# PSocC_Motor_Driver_Design_2.net
KiCad netlist of a schematic drawn in EAGLE
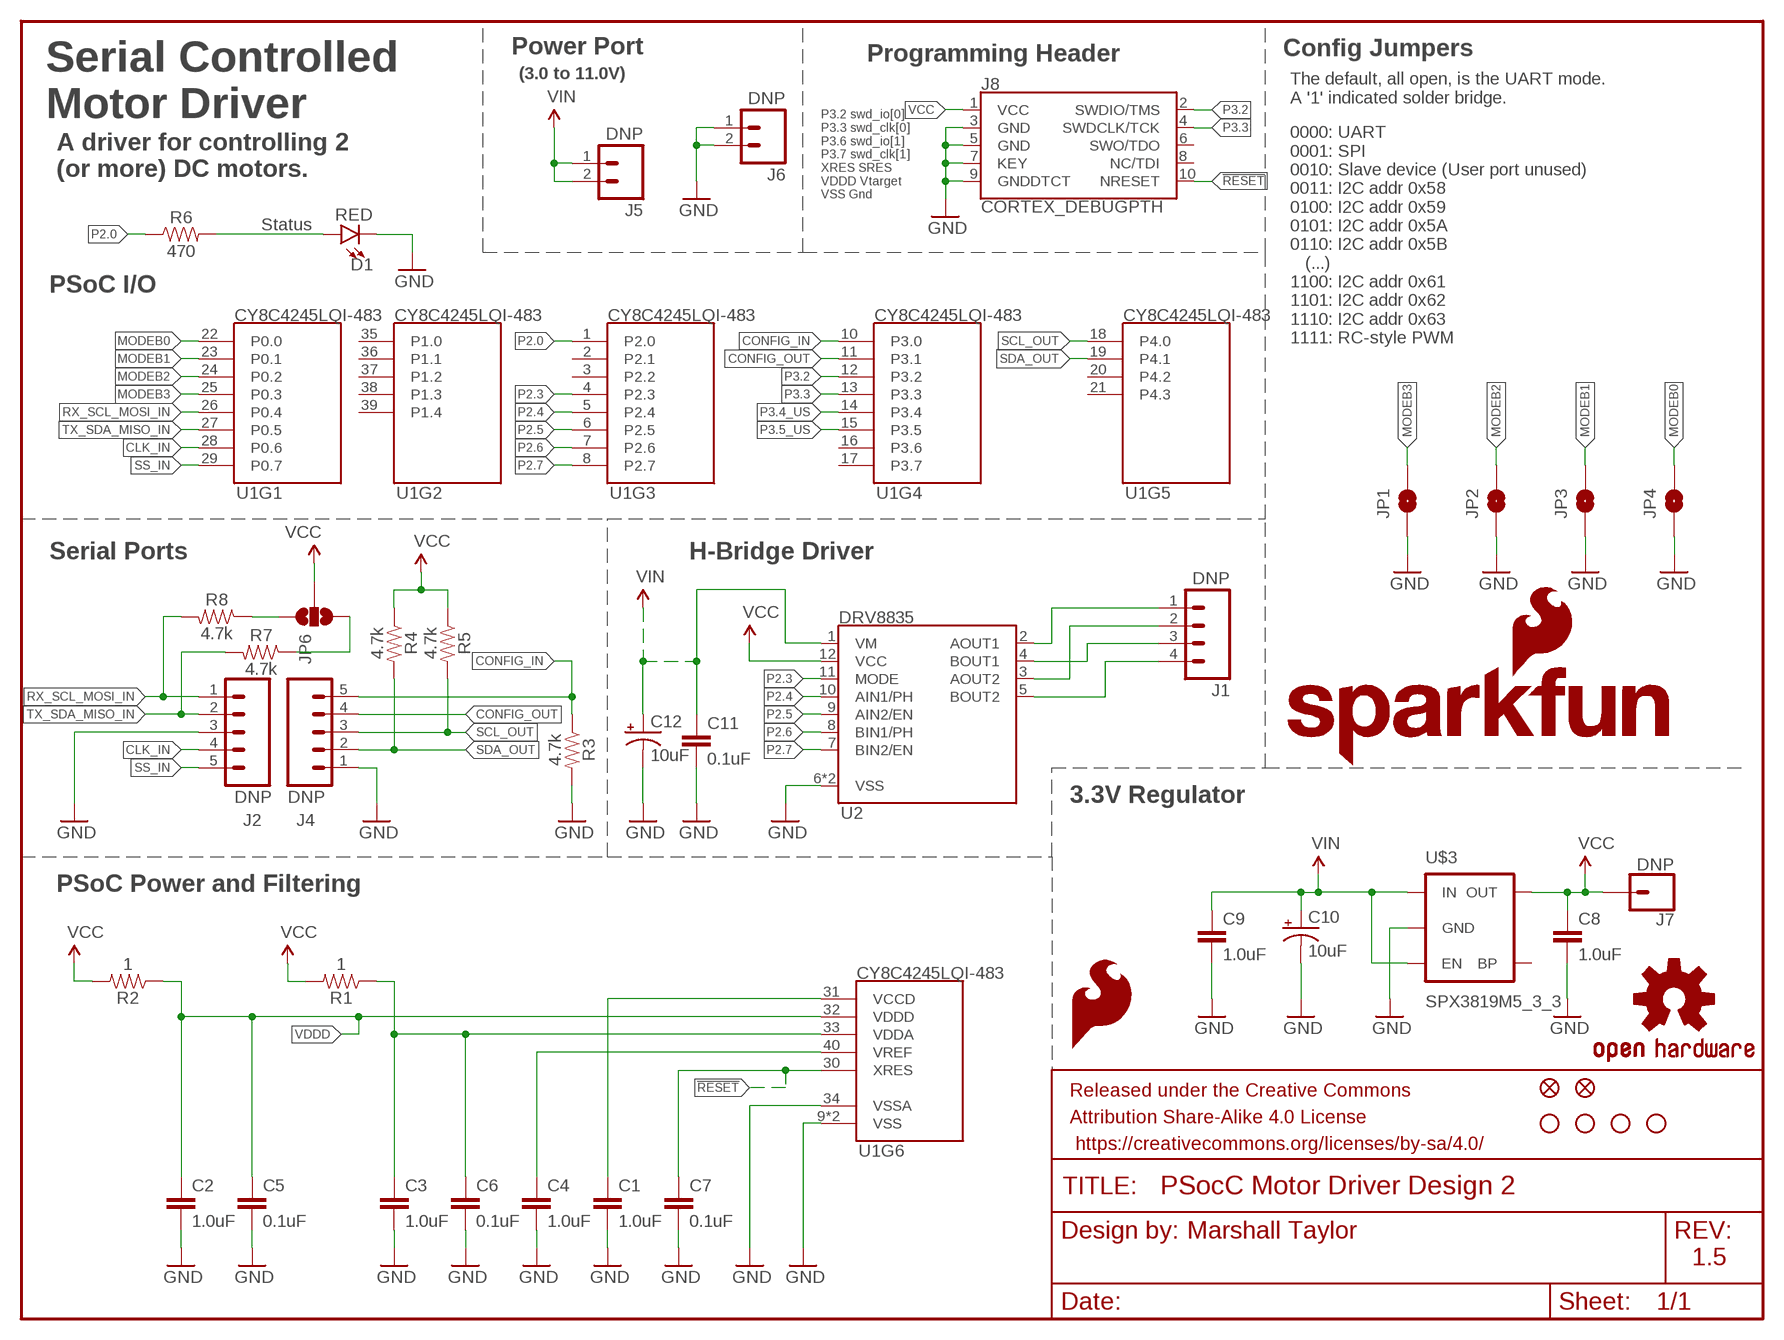
[diagram p0: schematic, sheet 1]

(export (version "E")
  (design (tool "Eeschema 10.0.6"))
  (components
    (comp (ref "C1")
      (value "1.0uF")
      (footprint "eagle-import:0402")
      (libsource (lib "eagle-import") (part "1.0UF-0402-16V-10%"))
    )
    (comp (ref "C2")
      (value "1.0uF")
      (footprint "eagle-import:0402")
      (libsource (lib "eagle-import") (part "1.0UF-0402-16V-10%"))
    )
    (comp (ref "C3")
      (value "1.0uF")
      (footprint "eagle-import:0402")
      (libsource (lib "eagle-import") (part "1.0UF-0402-16V-10%"))
    )
    (comp (ref "C4")
      (value "1.0uF")
      (footprint "eagle-import:0402")
      (libsource (lib "eagle-import") (part "1.0UF-0402-16V-10%"))
    )
    (comp (ref "C5")
      (value "0.1uF")
      (footprint "eagle-import:0402")
      (libsource (lib "eagle-import") (part "0.1UF-0402-16V-10%"))
    )
    (comp (ref "C6")
      (value "0.1uF")
      (footprint "eagle-import:0402")
      (libsource (lib "eagle-import") (part "0.1UF-0402-16V-10%"))
    )
    (comp (ref "C7")
      (value "0.1uF")
      (footprint "eagle-import:0402")
      (libsource (lib "eagle-import") (part "0.1UF-0402-16V-10%"))
    )
    (comp (ref "C8")
      (value "1.0uF")
      (footprint "eagle-import:0402")
      (libsource (lib "eagle-import") (part "1.0UF-0402-16V-10%"))
    )
    (comp (ref "C9")
      (value "1.0uF")
      (footprint "eagle-import:0402")
      (libsource (lib "eagle-import") (part "1.0UF-0402-16V-10%"))
    )
    (comp (ref "C10")
      (value "10uF")
      (footprint "eagle-import:EIA3216")
      (libsource (lib "eagle-import") (part "10UF-POLAR-EIA3216-16V-10%(TANT)"))
    )
    (comp (ref "C11")
      (value "0.1uF")
      (footprint "eagle-import:0402")
      (libsource (lib "eagle-import") (part "0.1UF-0402-16V-10%"))
    )
    (comp (ref "C12")
      (value "10uF")
      (footprint "eagle-import:EIA3216")
      (libsource (lib "eagle-import") (part "10UF-POLAR-EIA3216-16V-10%(TANT)"))
    )
    (comp (ref "D1")
      (value "RED")
      (footprint "eagle-import:LED-0603")
      (libsource (lib "eagle-import") (part "LED-RED0603"))
    )
    (comp (ref "FD1")
      (value "FIDUCIALUFIDUCIAL")
      (footprint "eagle-import:MICRO-FIDUCIAL")
      (libsource (lib "eagle-import") (part "FIDUCIALUFIDUCIAL"))
    )
    (comp (ref "FD2")
      (value "FIDUCIALUFIDUCIAL")
      (footprint "eagle-import:MICRO-FIDUCIAL")
      (libsource (lib "eagle-import") (part "FIDUCIALUFIDUCIAL"))
    )
    (comp (ref "FRAME1")
      (value "FRAME-LETTER")
      (footprint "eagle-import:CREATIVE_COMMONS")
      (libsource (lib "eagle-import") (part "FRAME-LETTER"))
    )
    (comp (ref "H1")
      (value "STAND-OFF")
      (footprint "eagle-import:STAND-OFF")
      (libsource (lib "eagle-import") (part "STAND-OFF"))
    )
    (comp (ref "H2")
      (value "STAND-OFF")
      (footprint "eagle-import:STAND-OFF")
      (libsource (lib "eagle-import") (part "STAND-OFF"))
    )
    (comp (ref "H3")
      (value "STAND-OFF")
      (footprint "eagle-import:STAND-OFF")
      (libsource (lib "eagle-import") (part "STAND-OFF"))
    )
    (comp (ref "H4")
      (value "STAND-OFF")
      (footprint "eagle-import:STAND-OFF")
      (libsource (lib "eagle-import") (part "STAND-OFF"))
    )
    (comp (ref "J1")
      (value "DNP")
      (footprint "eagle-import:1X04")
      (libsource (lib "eagle-import") (part "M04PTH"))
    )
    (comp (ref "J2")
      (value "DNP")
      (footprint "eagle-import:1X05")
      (libsource (lib "eagle-import") (part "M05PTH"))
    )
    (comp (ref "J4")
      (value "DNP")
      (footprint "eagle-import:1X05")
      (libsource (lib "eagle-import") (part "M05PTH"))
    )
    (comp (ref "J5")
      (value "DNP")
      (footprint "eagle-import:1X02")
      (libsource (lib "eagle-import") (part "M02PTH"))
    )
    (comp (ref "J6")
      (value "DNP")
      (footprint "eagle-import:1X02")
      (libsource (lib "eagle-import") (part "M02PTH"))
    )
    (comp (ref "J7")
      (value "DNP")
      (footprint "eagle-import:1X01")
      (libsource (lib "eagle-import") (part "CONN_01PTH"))
    )
    (comp (ref "J8")
      (value "CORTEX_DEBUGPTH")
      (footprint "eagle-import:2X5-PTH-1.27MM")
      (libsource (lib "eagle-import") (part "CORTEX_DEBUGPTH"))
    )
    (comp (ref "JP1")
      (value "JUMPER-PAD-2")
      (footprint "eagle-import:PAD-JUMPER-2-NO_YES_SILK")
      (libsource (lib "eagle-import") (part "JUMPER-PAD-2-NOYES_SILK"))
    )
    (comp (ref "JP2")
      (value "JUMPER-PAD-2")
      (footprint "eagle-import:PAD-JUMPER-2-NO_YES_SILK")
      (libsource (lib "eagle-import") (part "JUMPER-PAD-2-NOYES_SILK"))
    )
    (comp (ref "JP3")
      (value "JUMPER-PAD-2")
      (footprint "eagle-import:PAD-JUMPER-2-NO_YES_SILK")
      (libsource (lib "eagle-import") (part "JUMPER-PAD-2-NOYES_SILK"))
    )
    (comp (ref "JP4")
      (value "JUMPER-PAD-2")
      (footprint "eagle-import:PAD-JUMPER-2-NO_YES_SILK")
      (libsource (lib "eagle-import") (part "JUMPER-PAD-2-NOYES_SILK"))
    )
    (comp (ref "JP6")
      (value "JUMPER-PAD-3-NOYES_SILK")
      (footprint "eagle-import:PAD-JUMPER-3-NO_YES_SILK")
      (libsource (lib "eagle-import") (part "JUMPER-PAD-3-NOYES_SILK"))
    )
    (comp (ref "LOGO1")
      (value "SFE_LOGO_FLAME.1_INCH")
      (footprint "eagle-import:SFE_LOGO_FLAME_.1")
      (libsource (lib "eagle-import") (part "SFE_LOGO_FLAME.1_INCH"))
    )
    (comp (ref "LOGO2")
      (value "OSHW-LOGOMINI")
      (footprint "eagle-import:OSHW-LOGO-MINI")
      (libsource (lib "eagle-import") (part "OSHW-LOGOMINI"))
    )
    (comp (ref "LOGO3")
      (value "SFE_LOGO_NAME_FLAME.1_INCH")
      (footprint "eagle-import:SFE_LOGO_NAME_FLAME_.1")
      (libsource (lib "eagle-import") (part "SFE_LOGO_NAME_FLAME.1_INCH"))
    )
    (comp (ref "R1")
      (value "1")
      (footprint "eagle-import:0603")
      (libsource (lib "eagle-import") (part "1OHM-0603-1/10W-1%"))
    )
    (comp (ref "R2")
      (value "1")
      (footprint "eagle-import:0603")
      (libsource (lib "eagle-import") (part "1OHM-0603-1/10W-1%"))
    )
    (comp (ref "R3")
      (value "4.7k")
      (footprint "eagle-import:0603")
      (libsource (lib "eagle-import") (part "4.7KOHM-0603-1/10W-1%"))
    )
    (comp (ref "R4")
      (value "4.7k")
      (footprint "eagle-import:0603")
      (libsource (lib "eagle-import") (part "4.7KOHM-0603-1/10W-1%"))
    )
    (comp (ref "R5")
      (value "4.7k")
      (footprint "eagle-import:0603")
      (libsource (lib "eagle-import") (part "4.7KOHM-0603-1/10W-1%"))
    )
    (comp (ref "R6")
      (value "470")
      (footprint "eagle-import:0603")
      (libsource (lib "eagle-import") (part "470OHM-0603-1/10W-1%"))
    )
    (comp (ref "R7")
      (value "4.7k")
      (footprint "eagle-import:0603")
      (libsource (lib "eagle-import") (part "4.7KOHM-0603-1/10W-1%"))
    )
    (comp (ref "R8")
      (value "4.7k")
      (footprint "eagle-import:0603")
      (libsource (lib "eagle-import") (part "4.7KOHM-0603-1/10W-1%"))
    )
    (comp (ref "U$3")
      (value "SPX3819M5_3_3")
      (footprint "eagle-import:SOT-23-5-VREG")
      (libsource (lib "eagle-import") (part "SPX3819"))
    )
    (comp (ref "U1")
      (value "CY8C4245LQI-483")
      (footprint "eagle-import:QFN-40")
      (libsource (lib "eagle-import") (part "CY8C4245LQI"))
    )
    (comp (ref "U2")
      (value "DRV8835")
      (footprint "eagle-import:WSON-12")
      (fields (field (name "PROD_ID") "IC-13342"))
      (libsource (lib "eagle-import") (part "DRV883X"))
    )
  )
  (nets
    (net (code "1") (name "/~{RESET}") (class "Default")
      (node (ref "C7") (pin "1") (pinfunction "1_1") (pintype "passive"))
      (node (ref "J8") (pin "10") (pinfunction "NRESET_10") (pintype "bidirectional"))
      (node (ref "U1") (pin "30") (pinfunction "XRES_30") (pintype "bidirectional"))
    )
    (net (code "2") (name "CLK_IN") (class "Default")
      (node (ref "J2") (pin "4") (pinfunction "4_4") (pintype "passive"))
      (node (ref "U1") (pin "28") (pinfunction "P0.6_28") (pintype "bidirectional"))
    )
    (net (code "3") (name "CONFIG_IN") (class "Default")
      (node (ref "J4") (pin "5") (pinfunction "5_5") (pintype "passive"))
      (node (ref "R3") (pin "1") (pinfunction "1_1") (pintype "passive"))
      (node (ref "U1") (pin "10") (pinfunction "P3.0_10") (pintype "bidirectional"))
    )
    (net (code "4") (name "CONFIG_OUT") (class "Default")
      (node (ref "J4") (pin "4") (pinfunction "4_4") (pintype "passive"))
      (node (ref "U1") (pin "11") (pinfunction "P3.1_11") (pintype "bidirectional"))
    )
    (net (code "5") (name "GND") (class "Default")
      (node (ref "C1") (pin "2") (pinfunction "2_2") (pintype "passive"))
      (node (ref "C10") (pin "-") (pinfunction "-_-") (pintype "passive"))
      (node (ref "C11") (pin "2") (pinfunction "2_2") (pintype "passive"))
      (node (ref "C12") (pin "-") (pinfunction "-_-") (pintype "passive"))
      (node (ref "C2") (pin "2") (pinfunction "2_2") (pintype "passive"))
      (node (ref "C3") (pin "2") (pinfunction "2_2") (pintype "passive"))
      (node (ref "C4") (pin "2") (pinfunction "2_2") (pintype "passive"))
      (node (ref "C5") (pin "2") (pinfunction "2_2") (pintype "passive"))
      (node (ref "C6") (pin "2") (pinfunction "2_2") (pintype "passive"))
      (node (ref "C7") (pin "2") (pinfunction "2_2") (pintype "passive"))
      (node (ref "C8") (pin "2") (pinfunction "2_2") (pintype "passive"))
      (node (ref "C9") (pin "2") (pinfunction "2_2") (pintype "passive"))
      (node (ref "D1") (pin "C") (pinfunction "C_C") (pintype "passive"))
      (node (ref "J2") (pin "3") (pinfunction "3_3") (pintype "passive"))
      (node (ref "J4") (pin "1") (pinfunction "1_1") (pintype "passive"))
      (node (ref "J6") (pin "1") (pinfunction "1_1") (pintype "passive"))
      (node (ref "J6") (pin "2") (pinfunction "2_2") (pintype "passive"))
      (node (ref "J8") (pin "3") (pinfunction "GND_3") (pintype "bidirectional"))
      (node (ref "J8") (pin "5") (pinfunction "GND_5") (pintype "bidirectional"))
      (node (ref "J8") (pin "7") (pinfunction "KEY_7") (pintype "bidirectional"))
      (node (ref "J8") (pin "9") (pinfunction "GNDDTCT_9") (pintype "bidirectional"))
      (node (ref "JP1") (pin "1") (pinfunction "1_1") (pintype "passive"))
      (node (ref "JP2") (pin "1") (pinfunction "1_1") (pintype "passive"))
      (node (ref "JP3") (pin "1") (pinfunction "1_1") (pintype "passive"))
      (node (ref "JP4") (pin "1") (pinfunction "1_1") (pintype "passive"))
      (node (ref "R3") (pin "2") (pinfunction "2_2") (pintype "passive"))
      (node (ref "U$3") (pin "2") (pinfunction "GND_2") (pintype "input"))
      (node (ref "U1") (pin "34") (pinfunction "VSSA_34") (pintype "bidirectional"))
      (node (ref "U1") (pin "9") (pinfunction "VSS_9") (pintype "bidirectional"))
      (node (ref "U1") (pin "EP") (pinfunction "VSS_EP") (pintype "bidirectional"))
      (node (ref "U2") (pin "6") (pinfunction "VSS_6") (pintype "bidirectional"))
      (node (ref "U2") (pin "PAD") (pinfunction "VSS_PAD") (pintype "bidirectional"))
    )
    (net (code "6") (name "MODEB0") (class "Default")
      (node (ref "JP4") (pin "2") (pinfunction "2_2") (pintype "passive"))
      (node (ref "U1") (pin "22") (pinfunction "P0.0_22") (pintype "bidirectional"))
    )
    (net (code "7") (name "MODEB1") (class "Default")
      (node (ref "JP3") (pin "2") (pinfunction "2_2") (pintype "passive"))
      (node (ref "U1") (pin "23") (pinfunction "P0.1_23") (pintype "bidirectional"))
    )
    (net (code "8") (name "MODEB2") (class "Default")
      (node (ref "JP2") (pin "2") (pinfunction "2_2") (pintype "passive"))
      (node (ref "U1") (pin "24") (pinfunction "P0.2_24") (pintype "bidirectional"))
    )
    (net (code "9") (name "MODEB3") (class "Default")
      (node (ref "JP1") (pin "2") (pinfunction "2_2") (pintype "passive"))
      (node (ref "U1") (pin "25") (pinfunction "P0.3_25") (pintype "bidirectional"))
    )
    (net (code "10") (name "Net-(D1-PadA)") (class "Default")
      (node (ref "D1") (pin "A") (pinfunction "A_A") (pintype "passive"))
      (node (ref "R6") (pin "2") (pinfunction "2_2") (pintype "passive"))
    )
    (net (code "11") (name "Net-(JP6-Pad1)") (class "Default")
      (node (ref "JP6") (pin "1") (pinfunction "1_1") (pintype "passive"))
      (node (ref "R8") (pin "1") (pinfunction "1_1") (pintype "passive"))
    )
    (net (code "12") (name "Net-(JP6-Pad3)") (class "Default")
      (node (ref "JP6") (pin "3") (pinfunction "3_3") (pintype "passive"))
      (node (ref "R7") (pin "1") (pinfunction "1_1") (pintype "passive"))
    )
    (net (code "13") (name "Net-(U1F-VCCD)") (class "Default")
      (node (ref "C1") (pin "1") (pinfunction "1_1") (pintype "passive"))
      (node (ref "U1") (pin "31") (pinfunction "VCCD_31") (pintype "bidirectional"))
    )
    (net (code "14") (name "Net-(U1F-VDDA)") (class "Default")
      (node (ref "C3") (pin "1") (pinfunction "1_1") (pintype "passive"))
      (node (ref "C6") (pin "1") (pinfunction "1_1") (pintype "passive"))
      (node (ref "R1") (pin "1") (pinfunction "1_1") (pintype "passive"))
      (node (ref "U1") (pin "33") (pinfunction "VDDA_33") (pintype "bidirectional"))
    )
    (net (code "15") (name "Net-(U1F-VREF)") (class "Default")
      (node (ref "C4") (pin "1") (pinfunction "1_1") (pintype "passive"))
      (node (ref "U1") (pin "40") (pinfunction "VREF_40") (pintype "bidirectional"))
    )
    (net (code "16") (name "Net-(U2-AOUT1)") (class "Default")
      (node (ref "J1") (pin "1") (pinfunction "1_1") (pintype "passive"))
      (node (ref "U2") (pin "2") (pinfunction "AOUT1_2") (pintype "bidirectional"))
    )
    (net (code "17") (name "Net-(U2-AOUT2)") (class "Default")
      (node (ref "J1") (pin "2") (pinfunction "2_2") (pintype "passive"))
      (node (ref "U2") (pin "3") (pinfunction "AOUT2_3") (pintype "bidirectional"))
    )
    (net (code "18") (name "Net-(U2-BOUT1)") (class "Default")
      (node (ref "J1") (pin "3") (pinfunction "3_3") (pintype "passive"))
      (node (ref "U2") (pin "4") (pinfunction "BOUT1_4") (pintype "bidirectional"))
    )
    (net (code "19") (name "Net-(U2-BOUT2)") (class "Default")
      (node (ref "J1") (pin "4") (pinfunction "4_4") (pintype "passive"))
      (node (ref "U2") (pin "5") (pinfunction "BOUT2_5") (pintype "bidirectional"))
    )
    (net (code "20") (name "P2.0") (class "Default")
      (node (ref "R6") (pin "1") (pinfunction "1_1") (pintype "passive"))
      (node (ref "U1") (pin "1") (pinfunction "P2.0_1") (pintype "bidirectional"))
    )
    (net (code "21") (name "P2.3") (class "Default")
      (node (ref "U1") (pin "4") (pinfunction "P2.3_4") (pintype "bidirectional"))
      (node (ref "U2") (pin "11") (pinfunction "MODE_11") (pintype "bidirectional"))
    )
    (net (code "22") (name "P2.4") (class "Default")
      (node (ref "U1") (pin "5") (pinfunction "P2.4_5") (pintype "bidirectional"))
      (node (ref "U2") (pin "10") (pinfunction "AIN1/PH_10") (pintype "bidirectional"))
    )
    (net (code "23") (name "P2.5") (class "Default")
      (node (ref "U1") (pin "6") (pinfunction "P2.5_6") (pintype "bidirectional"))
      (node (ref "U2") (pin "9") (pinfunction "AIN2/EN_9") (pintype "bidirectional"))
    )
    (net (code "24") (name "P2.6") (class "Default")
      (node (ref "U1") (pin "7") (pinfunction "P2.6_7") (pintype "bidirectional"))
      (node (ref "U2") (pin "8") (pinfunction "BIN1/PH_8") (pintype "bidirectional"))
    )
    (net (code "25") (name "P2.7") (class "Default")
      (node (ref "U1") (pin "8") (pinfunction "P2.7_8") (pintype "bidirectional"))
      (node (ref "U2") (pin "7") (pinfunction "BIN2/EN_7") (pintype "bidirectional"))
    )
    (net (code "26") (name "P3.2") (class "Default")
      (node (ref "J8") (pin "2") (pinfunction "SWDIO/TMS_2") (pintype "bidirectional"))
      (node (ref "U1") (pin "12") (pinfunction "P3.2_12") (pintype "bidirectional"))
    )
    (net (code "27") (name "P3.3") (class "Default")
      (node (ref "J8") (pin "4") (pinfunction "SWDCLK/TCK_4") (pintype "bidirectional"))
      (node (ref "U1") (pin "13") (pinfunction "P3.3_13") (pintype "bidirectional"))
    )
    (net (code "28") (name "P3.4_US") (class "Default")
      (node (ref "U1") (pin "14") (pinfunction "P3.4_14") (pintype "bidirectional"))
    )
    (net (code "29") (name "P3.5_US") (class "Default")
      (node (ref "U1") (pin "15") (pinfunction "P3.5_15") (pintype "bidirectional"))
    )
    (net (code "30") (name "RX_SCL_MOSI_IN") (class "Default")
      (node (ref "J2") (pin "1") (pinfunction "1_1") (pintype "passive"))
      (node (ref "R8") (pin "2") (pinfunction "2_2") (pintype "passive"))
      (node (ref "U1") (pin "26") (pinfunction "P0.4_26") (pintype "bidirectional"))
    )
    (net (code "31") (name "SCL_OUT") (class "Default")
      (node (ref "J4") (pin "3") (pinfunction "3_3") (pintype "passive"))
      (node (ref "R5") (pin "2") (pinfunction "2_2") (pintype "passive"))
      (node (ref "U1") (pin "18") (pinfunction "P4.0_18") (pintype "bidirectional"))
    )
    (net (code "32") (name "SDA_OUT") (class "Default")
      (node (ref "J4") (pin "2") (pinfunction "2_2") (pintype "passive"))
      (node (ref "R4") (pin "2") (pinfunction "2_2") (pintype "passive"))
      (node (ref "U1") (pin "19") (pinfunction "P4.1_19") (pintype "bidirectional"))
    )
    (net (code "33") (name "SS_IN") (class "Default")
      (node (ref "J2") (pin "5") (pinfunction "5_5") (pintype "passive"))
      (node (ref "U1") (pin "29") (pinfunction "P0.7_29") (pintype "bidirectional"))
    )
    (net (code "34") (name "TX_SDA_MISO_IN") (class "Default")
      (node (ref "J2") (pin "2") (pinfunction "2_2") (pintype "passive"))
      (node (ref "R7") (pin "2") (pinfunction "2_2") (pintype "passive"))
      (node (ref "U1") (pin "27") (pinfunction "P0.5_27") (pintype "bidirectional"))
    )
    (net (code "35") (name "VCC") (class "Default")
      (node (ref "C8") (pin "1") (pinfunction "1_1") (pintype "passive"))
      (node (ref "J7") (pin "1") (pinfunction "1_1") (pintype "passive"))
      (node (ref "J8") (pin "1") (pinfunction "VCC_1") (pintype "bidirectional"))
      (node (ref "JP6") (pin "2") (pinfunction "2_2") (pintype "passive"))
      (node (ref "R1") (pin "2") (pinfunction "2_2") (pintype "passive"))
      (node (ref "R2") (pin "2") (pinfunction "2_2") (pintype "passive"))
      (node (ref "R4") (pin "1") (pinfunction "1_1") (pintype "passive"))
      (node (ref "R5") (pin "1") (pinfunction "1_1") (pintype "passive"))
      (node (ref "U$3") (pin "5") (pinfunction "OUT_5") (pintype "passive"))
      (node (ref "U2") (pin "12") (pinfunction "VCC_12") (pintype "bidirectional"))
    )
    (net (code "36") (name "VDDD") (class "Default")
      (node (ref "C2") (pin "1") (pinfunction "1_1") (pintype "passive"))
      (node (ref "C5") (pin "1") (pinfunction "1_1") (pintype "passive"))
      (node (ref "R2") (pin "1") (pinfunction "1_1") (pintype "passive"))
      (node (ref "U1") (pin "32") (pinfunction "VDDD_32") (pintype "bidirectional"))
    )
    (net (code "37") (name "VIN") (class "Default")
      (node (ref "C10") (pin "+") (pinfunction "+_+") (pintype "passive"))
      (node (ref "C11") (pin "1") (pinfunction "1_1") (pintype "passive"))
      (node (ref "C12") (pin "+") (pinfunction "+_+") (pintype "passive"))
      (node (ref "C9") (pin "1") (pinfunction "1_1") (pintype "passive"))
      (node (ref "J5") (pin "1") (pinfunction "1_1") (pintype "passive"))
      (node (ref "J5") (pin "2") (pinfunction "2_2") (pintype "passive"))
      (node (ref "U$3") (pin "1") (pinfunction "IN_1") (pintype "input"))
      (node (ref "U$3") (pin "3") (pinfunction "EN_3") (pintype "input"))
      (node (ref "U2") (pin "1") (pinfunction "VM_1") (pintype "bidirectional"))
    )
    (net (code "38") (name "unconnected-(J8-NC{slash}TDI-Pad8)") (class "Default")
      (node (ref "J8") (pin "8") (pinfunction "NC/TDI_8") (pintype "bidirectional"))
    )
    (net (code "39") (name "unconnected-(J8-SWO{slash}TDO-Pad6)") (class "Default")
      (node (ref "J8") (pin "6") (pinfunction "SWO/TDO_6") (pintype "bidirectional"))
    )
    (net (code "40") (name "unconnected-(U$3-BP-Pad4)") (class "Default")
      (node (ref "U$3") (pin "4") (pinfunction "BP_4") (pintype "input"))
    )
    (net (code "41") (name "unconnected-(U1B-P1.0-Pad35)") (class "Default")
      (node (ref "U1") (pin "35") (pinfunction "P1.0_35") (pintype "bidirectional"))
    )
    (net (code "42") (name "unconnected-(U1B-P1.1-Pad36)") (class "Default")
      (node (ref "U1") (pin "36") (pinfunction "P1.1_36") (pintype "bidirectional"))
    )
    (net (code "43") (name "unconnected-(U1B-P1.2-Pad37)") (class "Default")
      (node (ref "U1") (pin "37") (pinfunction "P1.2_37") (pintype "bidirectional"))
    )
    (net (code "44") (name "unconnected-(U1B-P1.3-Pad38)") (class "Default")
      (node (ref "U1") (pin "38") (pinfunction "P1.3_38") (pintype "bidirectional"))
    )
    (net (code "45") (name "unconnected-(U1B-P1.4-Pad39)") (class "Default")
      (node (ref "U1") (pin "39") (pinfunction "P1.4_39") (pintype "bidirectional"))
    )
    (net (code "46") (name "unconnected-(U1C-P2.1-Pad2)") (class "Default")
      (node (ref "U1") (pin "2") (pinfunction "P2.1_2") (pintype "bidirectional"))
    )
    (net (code "47") (name "unconnected-(U1C-P2.2-Pad3)") (class "Default")
      (node (ref "U1") (pin "3") (pinfunction "P2.2_3") (pintype "bidirectional"))
    )
    (net (code "48") (name "unconnected-(U1D-P3.6-Pad16)") (class "Default")
      (node (ref "U1") (pin "16") (pinfunction "P3.6_16") (pintype "bidirectional"))
    )
    (net (code "49") (name "unconnected-(U1D-P3.7-Pad17)") (class "Default")
      (node (ref "U1") (pin "17") (pinfunction "P3.7_17") (pintype "bidirectional"))
    )
    (net (code "50") (name "unconnected-(U1E-P4.2-Pad20)") (class "Default")
      (node (ref "U1") (pin "20") (pinfunction "P4.2_20") (pintype "bidirectional"))
    )
    (net (code "51") (name "unconnected-(U1E-P4.3-Pad21)") (class "Default")
      (node (ref "U1") (pin "21") (pinfunction "P4.3_21") (pintype "bidirectional"))
    )
  )
)
